# MCU.net
KiCad netlist of a schematic drawn in Altium Designer
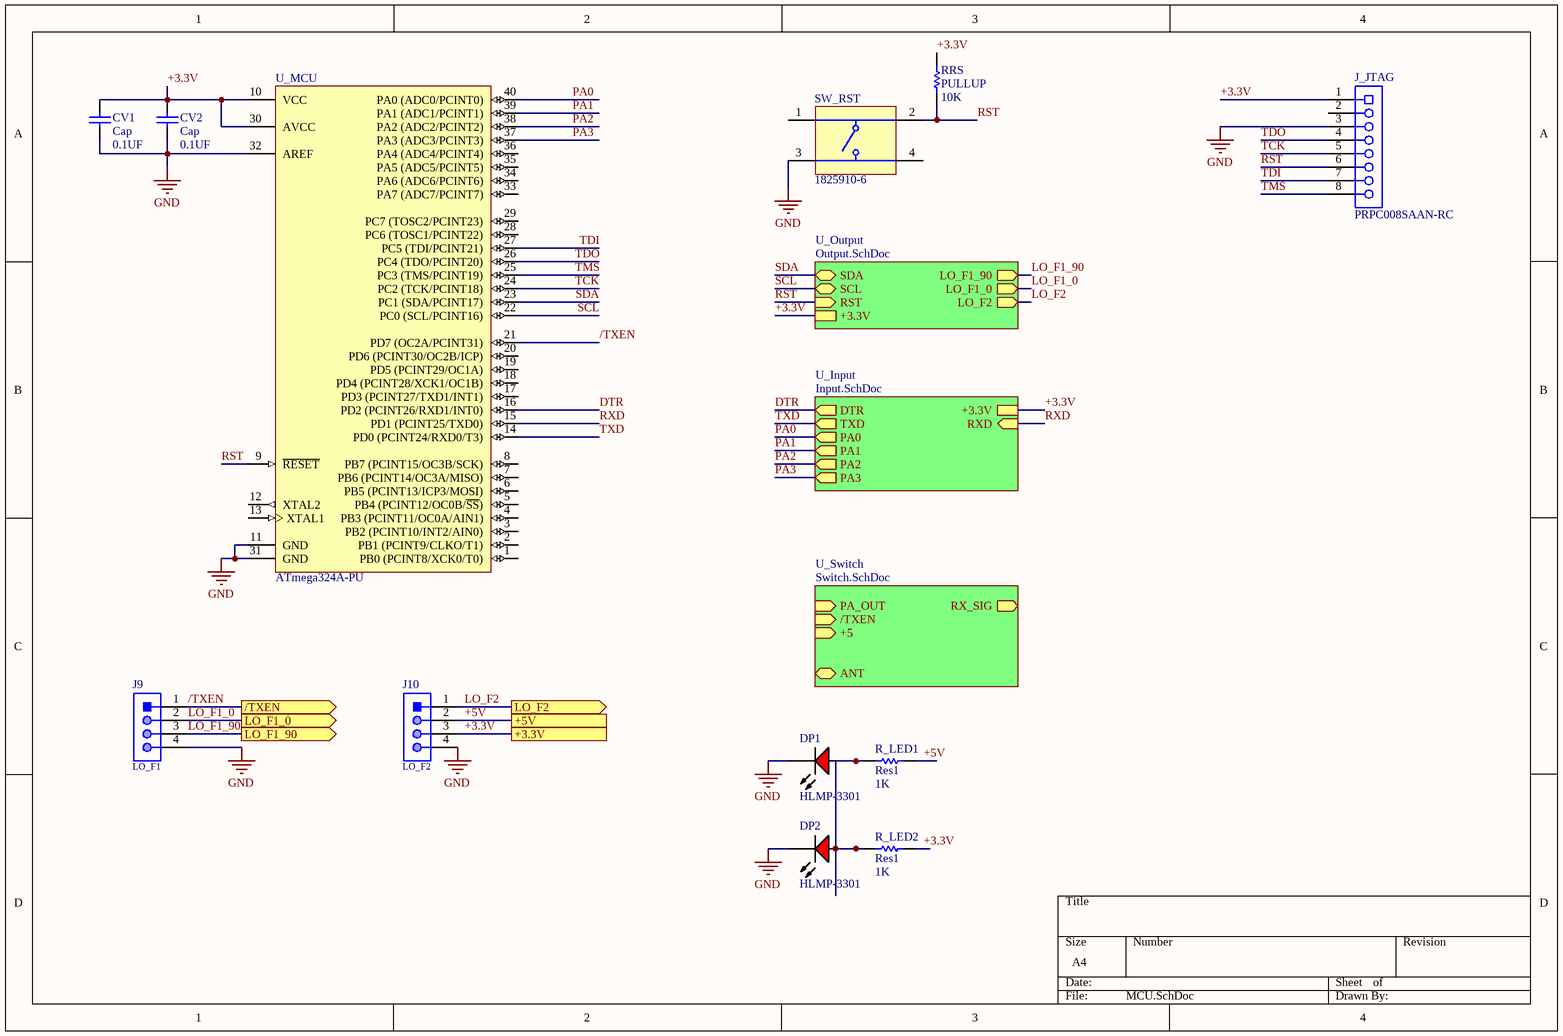
[diagram p0: MCU.SchDoc]

(export (version "E")
  (design (tool "Eeschema 10.0.6"))
  (components
    (comp (ref "CV1")
      (value "Cap")
      (footprint "1206")
      (description "Capacitor")
      (fields
        (field (name "ALTIUM_VALUE") "0.1UF")
        (field (name "MANUFACTURER PART NUMBER") "885012208087")
        (field (name "PUBLISHER") "Altium Limited")
      )
      (libsource (lib "ECE295-Capacitors-SMT") (part "CAP CER 0.1UF 50V X7R 1206"))
    )
    (comp (ref "CV2")
      (value "Cap")
      (footprint "1206")
      (description "Capacitor")
      (fields
        (field (name "ALTIUM_VALUE") "0.1UF")
        (field (name "MANUFACTURER PART NUMBER") "885012208087")
        (field (name "PUBLISHER") "Altium Limited")
      )
      (libsource (lib "ECE295-Capacitors-SMT") (part "CAP CER 0.1UF 50V X7R 1206"))
    )
    (comp (ref "DP1")
      (value "HLMP-3301")
      (footprint "AVAG-HLMP-3301-2")
      (description "T-1 3/4 (5 mm) Diffused LED Lamp, 1.9 V, -40 to 100 degC, 2-Pin THD, RoHS, Bulk")
      (fields (field (name "MANUFACTURER") "Avago"))
      (libsource (lib "Altium Content Vault") (part "LED-RED-K1A2-2"))
    )
    (comp (ref "DP2")
      (value "HLMP-3301")
      (footprint "AVAG-HLMP-3301-2")
      (description "T-1 3/4 (5 mm) Diffused LED Lamp, 1.9 V, -40 to 100 degC, 2-Pin THD, RoHS, Bulk")
      (fields (field (name "MANUFACTURER") "Avago"))
      (libsource (lib "Altium Content Vault") (part "LED-RED-K1A2-2"))
    )
    (comp (ref "J9")
      (value "LO_F1")
      (footprint "61300411121")
      (description "THT Vertical Pin Header WR-PHD, Pitch 2.54 mm, Single Row, 4 pins")
      (fields
        (field (name "MANUFACTURER") "Wurth Elektronik")
        (field (name "PART NUMBER") "61300411121")
        (field (name "PUBLISHER") "WurthElektronik")
      )
      (libsource (lib "Altium Content Vault") (part "WE-CN-1P-M-R4"))
    )
    (comp (ref "J10")
      (value "LO_F2")
      (footprint "61300411121")
      (description "THT Vertical Pin Header WR-PHD, Pitch 2.54 mm, Single Row, 4 pins")
      (fields
        (field (name "MANUFACTURER") "Wurth Elektronik")
        (field (name "PART NUMBER") "61300411121")
        (field (name "PUBLISHER") "WurthElektronik")
      )
      (libsource (lib "Altium Content Vault") (part "WE-CN-1P-M-R4"))
    )
    (comp (ref "J_JTAG")
      (value "PRPC008SAAN-RC")
      (footprint "SLIN-PPPC081LFBN-RC_V")
      (libsource (lib "Altium Content Vault") (part "CN-1P-F-R8"))
    )
    (comp (ref "RRS")
      (value "PULLUP")
      (footprint "AXIAL-0.1-RES")
      (description "Resistor")
      (fields
        (field (name "ALTIUM_VALUE") "10K")
        (field (name "MANUFACTURER PART NUMBER") "CFR-25JB-52-10K")
        (field (name "TOLERANCE") "0.05")
        (field (name "PUBLISHER") "Altium Limited")
      )
      (libsource (lib "ECE295-Resistors-TH") (part "RES 10K OHM 5% 1/4W AXIAL"))
    )
    (comp (ref "R_LED1")
      (value "Res1")
      (footprint "AXIAL-0.1-RES")
      (description "Resistor")
      (fields
        (field (name "MANUFACTURER PART NUMBER") "CFR-25JB-52-1K")
        (field (name "TOLERANCE") "0.05")
        (field (name "ALTIUM_VALUE") "1K")
        (field (name "PUBLISHER") "Altium Limited")
      )
      (libsource (lib "ECE295-Resistors-TH") (part "RES 1K OHM 5% 1/4W AXIAL"))
    )
    (comp (ref "R_LED2")
      (value "Res1")
      (footprint "AXIAL-0.1-RES")
      (description "Resistor")
      (fields
        (field (name "MANUFACTURER PART NUMBER") "CFR-25JB-52-1K")
        (field (name "TOLERANCE") "0.05")
        (field (name "ALTIUM_VALUE") "1K")
        (field (name "PUBLISHER") "Altium Limited")
      )
      (libsource (lib "ECE295-Resistors-TH") (part "RES 1K OHM 5% 1/4W AXIAL"))
    )
    (comp (ref "SW_RST")
      (value "1825910-6")
      (footprint "TECO-1825910-6_V")
      (description "Tact Switch, SPST-NO, 0.05 A, -35 to 85 degC, 4-Pin THD, RoHS, Bulk")
      (fields (field (name "MANUFACTURER") "TE Connectivity"))
      (libsource (lib "Altium Content Vault") (part "SW-SPST-4_A"))
    )
    (comp (ref "U_MCU")
      (value "ATmega324A-PU")
      (footprint "40P6")
      (libsource (lib "Altium Content Vault") (part "MC-8B-ATM128-IL40"))
    )
  )
  (nets
    (net (code "1") (name "/+3.3V") (class "Default")
      (node (ref "CV1") (pin "2") (pinfunction "2_2") (pintype "passive"))
      (node (ref "CV2") (pin "2") (pinfunction "2_2") (pintype "passive"))
      (node (ref "J10") (pin "3") (pinfunction "3_3") (pintype "passive"))
      (node (ref "J_JTAG") (pin "1") (pinfunction "1_1") (pintype "passive"))
      (node (ref "RRS") (pin "2") (pinfunction "2_2") (pintype "passive"))
      (node (ref "R_LED2") (pin "2") (pinfunction "2_2") (pintype "passive"))
      (node (ref "U_MCU") (pin "10") (pinfunction "VCC_10") (pintype "power_in"))
      (node (ref "U_MCU") (pin "30") (pinfunction "AVCC_30") (pintype "power_in"))
    )
    (net (code "3") (name "/+5V") (class "Default")
      (node (ref "J10") (pin "2") (pinfunction "2_2") (pintype "passive"))
      (node (ref "R_LED1") (pin "2") (pinfunction "2_2") (pintype "passive"))
    )
    (net (code "5") (name "/DTR") (class "Default")
      (node (ref "U_MCU") (pin "16") (pinfunction "PD2_(PCINT26/RXD1/INT0)_16") (pintype "bidirectional"))
    )
    (net (code "6") (name "/LO_F1_0") (class "Default")
      (node (ref "J9") (pin "2") (pinfunction "2_2") (pintype "passive"))
    )
    (net (code "7") (name "/LO_F1_90") (class "Default")
      (node (ref "J9") (pin "3") (pinfunction "3_3") (pintype "passive"))
    )
    (net (code "8") (name "/LO_F2") (class "Default")
      (node (ref "J10") (pin "1") (pinfunction "1_1") (pintype "passive"))
    )
    (net (code "9") (name "/PA0") (class "Default")
      (node (ref "U_MCU") (pin "40") (pinfunction "PA0_(ADC0/PCINT0)_40") (pintype "bidirectional"))
    )
    (net (code "10") (name "/PA1") (class "Default")
      (node (ref "U_MCU") (pin "39") (pinfunction "PA1_(ADC1/PCINT1)_39") (pintype "bidirectional"))
    )
    (net (code "11") (name "/PA2") (class "Default")
      (node (ref "U_MCU") (pin "38") (pinfunction "PA2_(ADC2/PCINT2)_38") (pintype "bidirectional"))
    )
    (net (code "12") (name "/PA3") (class "Default")
      (node (ref "U_MCU") (pin "37") (pinfunction "PA3_(ADC3/PCINT3)_37") (pintype "bidirectional"))
    )
    (net (code "14") (name "/RST") (class "Default")
      (node (ref "J_JTAG") (pin "6") (pinfunction "6_6") (pintype "passive"))
      (node (ref "RRS") (pin "1") (pinfunction "1_1") (pintype "passive"))
      (node (ref "SW_RST") (pin "2") (pinfunction "2_2") (pintype "passive"))
      (node (ref "U_MCU") (pin "9") (pinfunction "~{RESET}_9") (pintype "input"))
    )
    (net (code "15") (name "/RXD") (class "Default")
      (node (ref "U_MCU") (pin "15") (pinfunction "PD1_(PCINT25/TXD0)_15") (pintype "bidirectional"))
    )
    (net (code "17") (name "/SCL") (class "Default")
      (node (ref "U_MCU") (pin "22") (pinfunction "PC0_(SCL/PCINT16)_22") (pintype "bidirectional"))
    )
    (net (code "18") (name "/SDA") (class "Default")
      (node (ref "U_MCU") (pin "23") (pinfunction "PC1_(SDA/PCINT17)_23") (pintype "bidirectional"))
    )
    (net (code "19") (name "/TCK") (class "Default")
      (node (ref "J_JTAG") (pin "5") (pinfunction "5_5") (pintype "passive"))
      (node (ref "U_MCU") (pin "24") (pinfunction "PC2_(TCK/PCINT18)_24") (pintype "bidirectional"))
    )
    (net (code "20") (name "/TDI") (class "Default")
      (node (ref "J_JTAG") (pin "7") (pinfunction "7_7") (pintype "passive"))
      (node (ref "U_MCU") (pin "27") (pinfunction "PC5_(TDI/PCINT21)_27") (pintype "bidirectional"))
    )
    (net (code "21") (name "/TDO") (class "Default")
      (node (ref "J_JTAG") (pin "4") (pinfunction "4_4") (pintype "passive"))
      (node (ref "U_MCU") (pin "26") (pinfunction "PC4_(TDO/PCINT20)_26") (pintype "bidirectional"))
    )
    (net (code "22") (name "/TMS") (class "Default")
      (node (ref "J_JTAG") (pin "8") (pinfunction "8_8") (pintype "passive"))
      (node (ref "U_MCU") (pin "25") (pinfunction "PC3_(TMS/PCINT19)_25") (pintype "bidirectional"))
    )
    (net (code "23") (name "/TXD") (class "Default")
      (node (ref "U_MCU") (pin "14") (pinfunction "PD0_(PCINT24/RXD0/T3)_14") (pintype "bidirectional"))
    )
    (net (code "24") (name "/{slash}TXEN") (class "Default")
      (node (ref "J9") (pin "1") (pinfunction "1_1") (pintype "passive"))
      (node (ref "U_MCU") (pin "21") (pinfunction "PD7_(OC2A/PCINT31)_21") (pintype "bidirectional"))
    )
    (net (code "26") (name "GND") (class "Default")
      (node (ref "CV1") (pin "1") (pinfunction "1_1") (pintype "passive"))
      (node (ref "CV2") (pin "1") (pinfunction "1_1") (pintype "passive"))
      (node (ref "DP1") (pin "1") (pinfunction "K_1") (pintype "passive"))
      (node (ref "DP2") (pin "1") (pinfunction "K_1") (pintype "passive"))
      (node (ref "J10") (pin "4") (pinfunction "4_4") (pintype "passive"))
      (node (ref "J9") (pin "4") (pinfunction "4_4") (pintype "passive"))
      (node (ref "J_JTAG") (pin "3") (pinfunction "3_3") (pintype "passive"))
      (node (ref "SW_RST") (pin "3") (pinfunction "3_3") (pintype "passive"))
      (node (ref "U_MCU") (pin "11") (pinfunction "GND_11") (pintype "power_in"))
      (node (ref "U_MCU") (pin "31") (pinfunction "GND_31") (pintype "power_in"))
      (node (ref "U_MCU") (pin "32") (pinfunction "AREF_32") (pintype "power_in"))
    )
    (net (code "27") (name "Net-(DP1-A)") (class "Default")
      (node (ref "DP1") (pin "2") (pinfunction "A_2") (pintype "passive"))
      (node (ref "DP2") (pin "2") (pinfunction "A_2") (pintype "passive"))
      (node (ref "R_LED1") (pin "1") (pinfunction "1_1") (pintype "passive"))
      (node (ref "R_LED2") (pin "1") (pinfunction "1_1") (pintype "passive"))
    )
    (net (code "28") (name "unconnected-(J_JTAG-Pad2)") (class "Default")
      (node (ref "J_JTAG") (pin "2") (pinfunction "2_2") (pintype "passive"))
    )
    (net (code "29") (name "unconnected-(SW_RST-Pad1)") (class "Default")
      (node (ref "SW_RST") (pin "1") (pinfunction "1_1") (pintype "passive"))
    )
    (net (code "30") (name "unconnected-(SW_RST-Pad4)") (class "Default")
      (node (ref "SW_RST") (pin "4") (pinfunction "4_4") (pintype "passive"))
    )
    (net (code "31") (name "unconnected-(U_MCU-PA4_(ADC4{slash}PCINT4)-Pad36)") (class "Default")
      (node (ref "U_MCU") (pin "36") (pinfunction "PA4_(ADC4/PCINT4)_36") (pintype "bidirectional"))
    )
    (net (code "32") (name "unconnected-(U_MCU-PA5_(ADC5{slash}PCINT5)-Pad35)") (class "Default")
      (node (ref "U_MCU") (pin "35") (pinfunction "PA5_(ADC5/PCINT5)_35") (pintype "bidirectional"))
    )
    (net (code "33") (name "unconnected-(U_MCU-PA6_(ADC6{slash}PCINT6)-Pad34)") (class "Default")
      (node (ref "U_MCU") (pin "34") (pinfunction "PA6_(ADC6/PCINT6)_34") (pintype "bidirectional"))
    )
    (net (code "34") (name "unconnected-(U_MCU-PA7_(ADC7{slash}PCINT7)-Pad33)") (class "Default")
      (node (ref "U_MCU") (pin "33") (pinfunction "PA7_(ADC7/PCINT7)_33") (pintype "bidirectional"))
    )
    (net (code "35") (name "unconnected-(U_MCU-PB0_(PCINT8{slash}XCK0{slash}T0)-Pad1)") (class "Default")
      (node (ref "U_MCU") (pin "1") (pinfunction "PB0_(PCINT8/XCK0/T0)_1") (pintype "bidirectional"))
    )
    (net (code "36") (name "unconnected-(U_MCU-PB1_(PCINT9{slash}CLKO{slash}T1)-Pad2)") (class "Default")
      (node (ref "U_MCU") (pin "2") (pinfunction "PB1_(PCINT9/CLKO/T1)_2") (pintype "bidirectional"))
    )
    (net (code "37") (name "unconnected-(U_MCU-PB2_(PCINT10{slash}INT2{slash}AIN0)-Pad3)") (class "Default")
      (node (ref "U_MCU") (pin "3") (pinfunction "PB2_(PCINT10/INT2/AIN0)_3") (pintype "bidirectional"))
    )
    (net (code "38") (name "unconnected-(U_MCU-PB3_(PCINT11{slash}OC0A{slash}AIN1)-Pad4)") (class "Default")
      (node (ref "U_MCU") (pin "4") (pinfunction "PB3_(PCINT11/OC0A/AIN1)_4") (pintype "bidirectional"))
    )
    (net (code "39") (name "unconnected-(U_MCU-PB4_(PCINT12{slash}OC0B{slash}~{SS})-Pad5)") (class "Default")
      (node (ref "U_MCU") (pin "5") (pinfunction "PB4_(PCINT12/OC0B/~{SS})_5") (pintype "bidirectional"))
    )
    (net (code "40") (name "unconnected-(U_MCU-PB5_(PCINT13{slash}ICP3{slash}MOSI)-Pad6)") (class "Default")
      (node (ref "U_MCU") (pin "6") (pinfunction "PB5_(PCINT13/ICP3/MOSI)_6") (pintype "bidirectional"))
    )
    (net (code "41") (name "unconnected-(U_MCU-PB6_(PCINT14{slash}OC3A{slash}MISO)-Pad7)") (class "Default")
      (node (ref "U_MCU") (pin "7") (pinfunction "PB6_(PCINT14/OC3A/MISO)_7") (pintype "bidirectional"))
    )
    (net (code "42") (name "unconnected-(U_MCU-PB7_(PCINT15{slash}OC3B{slash}SCK)-Pad8)") (class "Default")
      (node (ref "U_MCU") (pin "8") (pinfunction "PB7_(PCINT15/OC3B/SCK)_8") (pintype "bidirectional"))
    )
    (net (code "43") (name "unconnected-(U_MCU-PC6_(TOSC1{slash}PCINT22)-Pad28)") (class "Default")
      (node (ref "U_MCU") (pin "28") (pinfunction "PC6_(TOSC1/PCINT22)_28") (pintype "bidirectional"))
    )
    (net (code "44") (name "unconnected-(U_MCU-PC7_(TOSC2{slash}PCINT23)-Pad29)") (class "Default")
      (node (ref "U_MCU") (pin "29") (pinfunction "PC7_(TOSC2/PCINT23)_29") (pintype "bidirectional"))
    )
    (net (code "45") (name "unconnected-(U_MCU-PD3_(PCINT27{slash}TXD1{slash}INT1)-Pad17)") (class "Default")
      (node (ref "U_MCU") (pin "17") (pinfunction "PD3_(PCINT27/TXD1/INT1)_17") (pintype "bidirectional"))
    )
    (net (code "46") (name "unconnected-(U_MCU-PD4_(PCINT28{slash}XCK1{slash}OC1B)-Pad18)") (class "Default")
      (node (ref "U_MCU") (pin "18") (pinfunction "PD4_(PCINT28/XCK1/OC1B)_18") (pintype "bidirectional"))
    )
    (net (code "47") (name "unconnected-(U_MCU-PD5_(PCINT29{slash}OC1A)-Pad19)") (class "Default")
      (node (ref "U_MCU") (pin "19") (pinfunction "PD5_(PCINT29/OC1A)_19") (pintype "bidirectional"))
    )
    (net (code "48") (name "unconnected-(U_MCU-PD6_(PCINT30{slash}OC2B{slash}ICP)-Pad20)") (class "Default")
      (node (ref "U_MCU") (pin "20") (pinfunction "PD6_(PCINT30/OC2B/ICP)_20") (pintype "bidirectional"))
    )
    (net (code "49") (name "unconnected-(U_MCU-XTAL1-Pad13)") (class "Default")
      (node (ref "U_MCU") (pin "13") (pinfunction "XTAL1_13") (pintype "input"))
    )
    (net (code "50") (name "unconnected-(U_MCU-XTAL2-Pad12)") (class "Default")
      (node (ref "U_MCU") (pin "12") (pinfunction "XTAL2_12") (pintype "output"))
    )
  )
)
